# Amplifier.net
KiCad netlist of a schematic drawn in Altium Designer
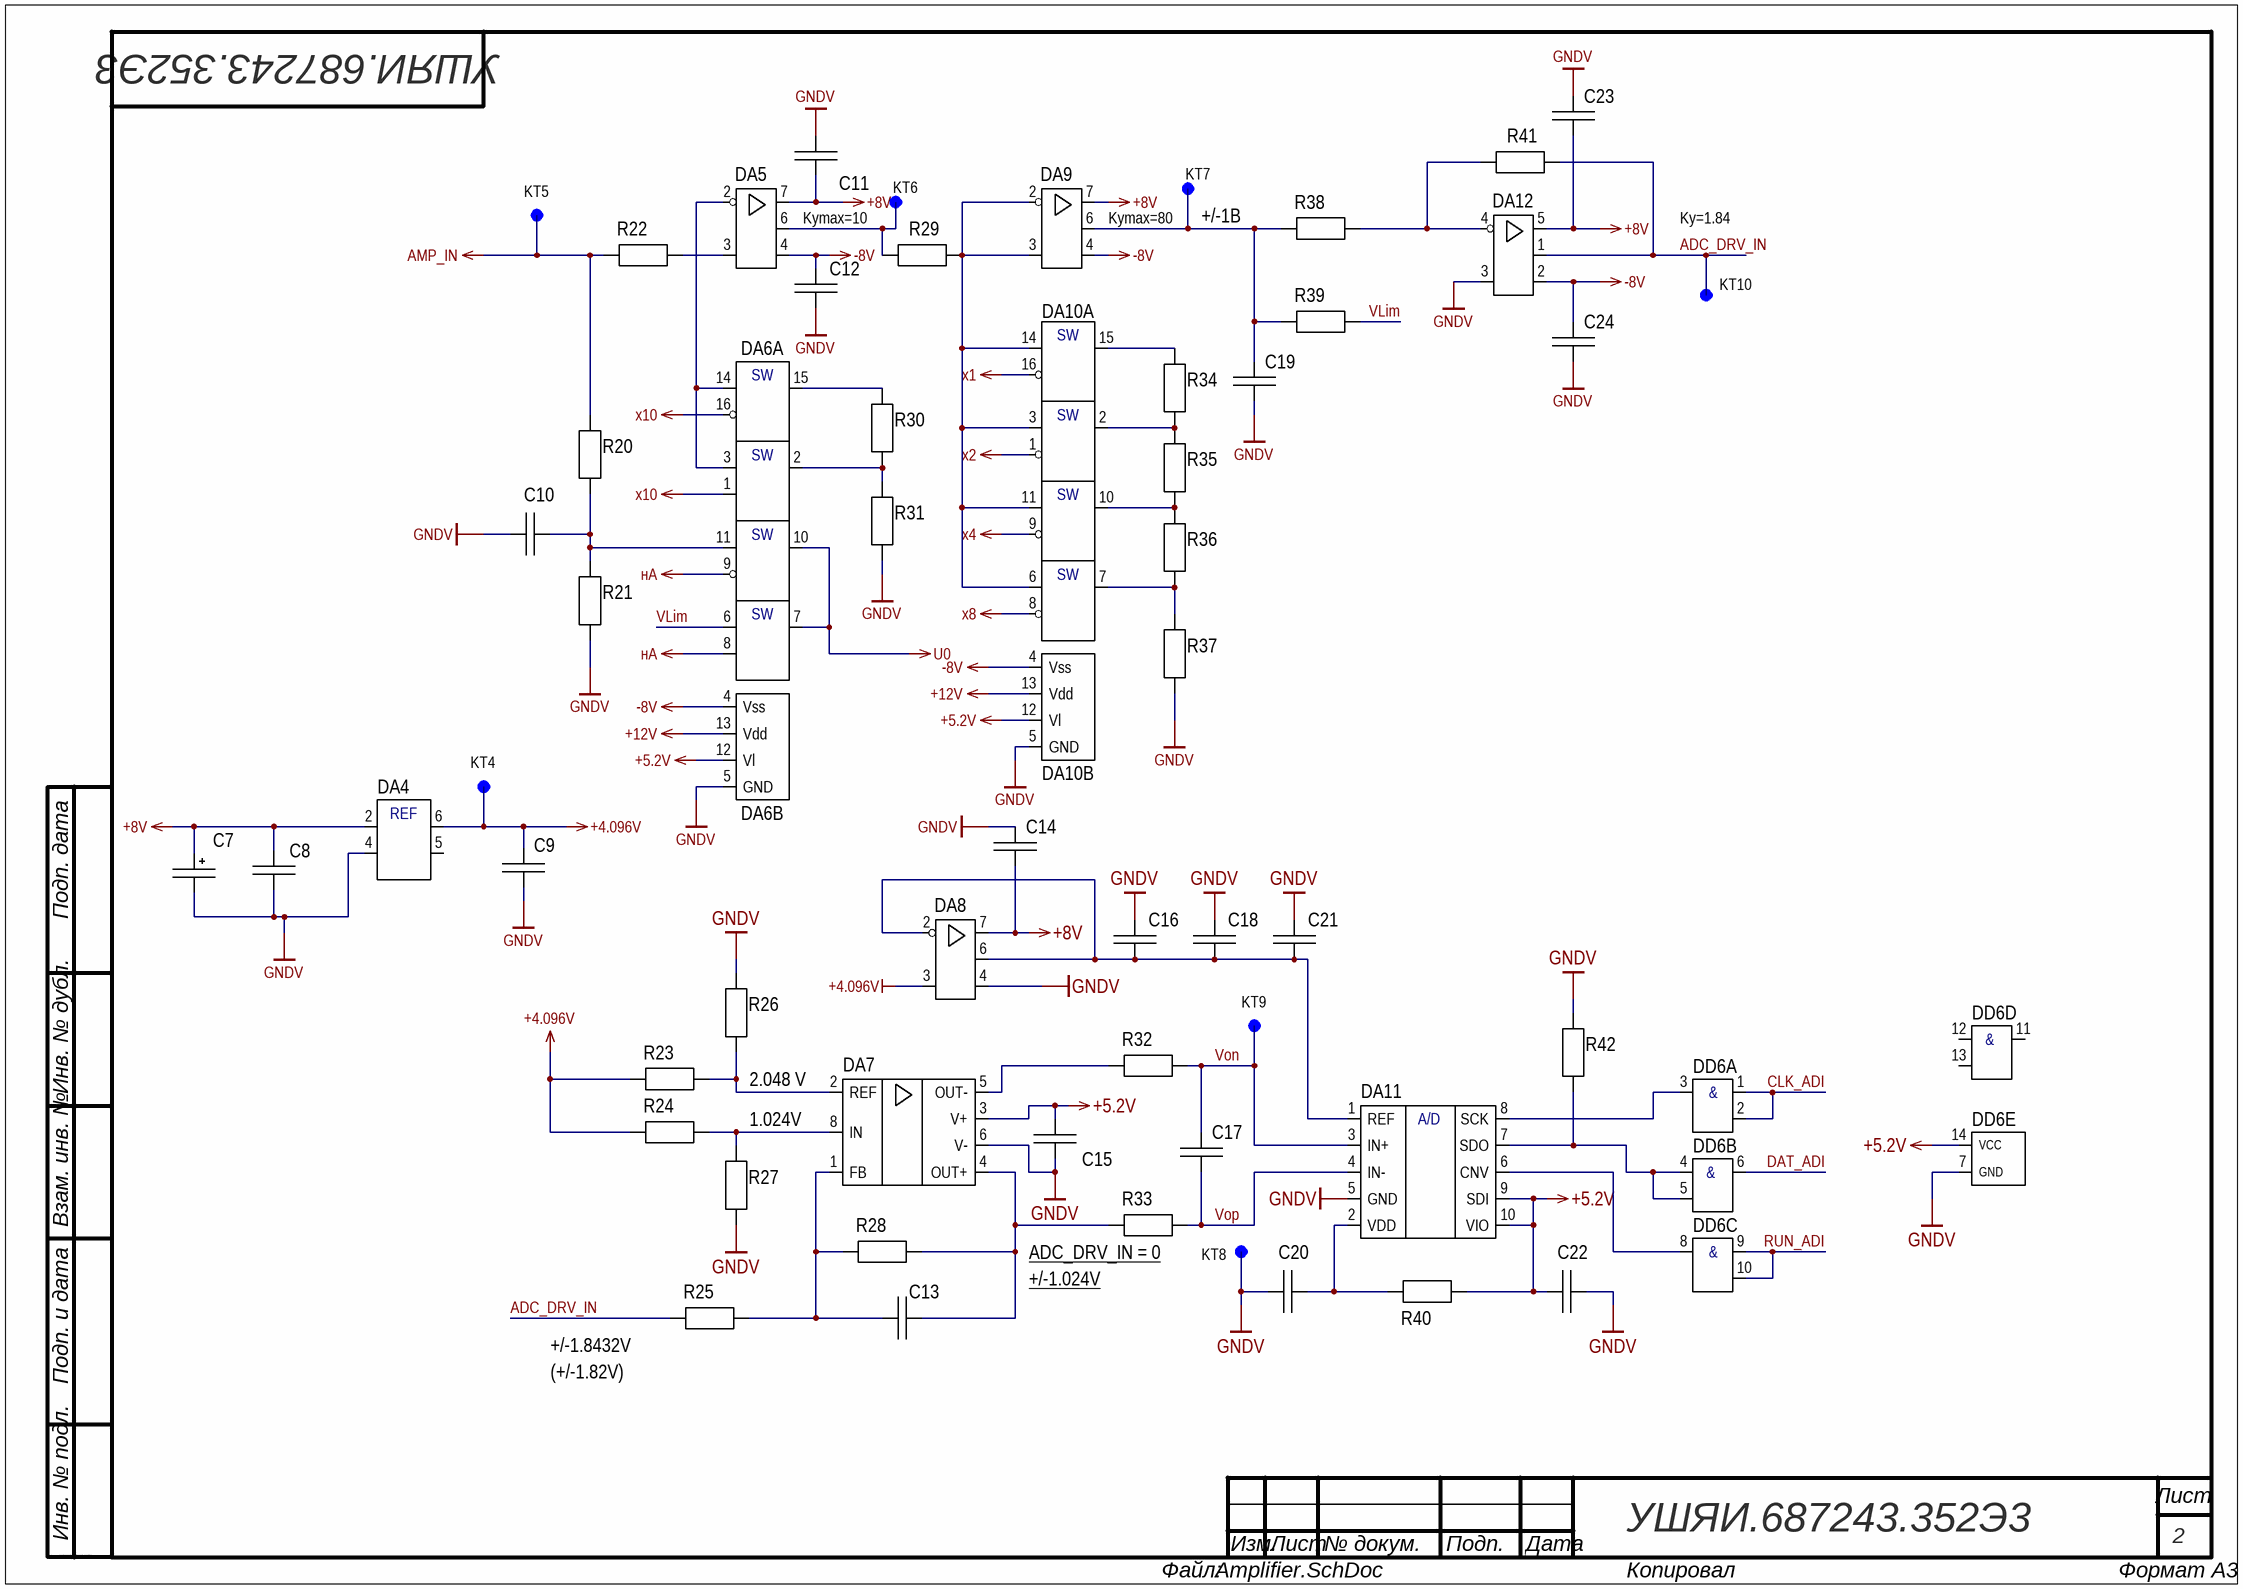
[diagram p0: Amplifier.SchDoc]

(export (version "E")
  (design (tool "Eeschema 10.0.6"))
  (components
    (comp (ref "C7")
      (value "JRB-50В-4,7мкФ")
      (footprint "CAP TH ALUM ELEC D5.00mm S2.00mm H11.00mm")
      (libsource (lib "МНИПИ_Конденсаторы") (part "JRB-50В-4,7мкФ"))
    )
    (comp (ref "C8")
      (value "1206-X7R-50 B-0,1 мкФ+-10%")
      (footprint "standard-case:CAP: 1206")
      (libsource (lib "МНИПИ_Конденсаторы") (part "1206-X7R-50 B-0,1 мкФ+-10%"))
    )
    (comp (ref "C9")
      (value "0805-X7R-25 В-0,1 мкФ +-10%")
      (footprint "standard-case:CAP: 0805")
      (libsource (lib "МНИПИ_Конденсаторы") (part "0805-X7R-25 В-0,1 мкФ +-10%"))
    )
    (comp (ref "C10")
      (value "1206-X7R-50 B-0,01 мкФ+-10%")
      (footprint "standard-case:CAP: 1206")
      (libsource (lib "МНИПИ_Конденсаторы") (part "1206-X7R-50 B-0,01 мкФ+-10%"))
    )
    (comp (ref "C11")
      (value "1206-X7R-50 B-0,1 мкФ+-10%")
      (footprint "standard-case:CAP: 1206")
      (libsource (lib "МНИПИ_Конденсаторы") (part "1206-X7R-50 B-0,1 мкФ+-10%"))
    )
    (comp (ref "C12")
      (value "1206-X7R-50 B-0,1 мкФ+-10%")
      (footprint "standard-case:CAP: 1206")
      (libsource (lib "МНИПИ_Конденсаторы") (part "1206-X7R-50 B-0,1 мкФ+-10%"))
    )
    (comp (ref "C13")
      (value "0805-C0G-50 В-240 пФ +-5%")
      (footprint "standard-case:CAP: 0805")
      (libsource (lib "МНИПИ_Конденсаторы") (part "0805-C0G-50 В-240 пФ +-5%"))
    )
    (comp (ref "C14")
      (value "1206-X7R-50 B-0,1 мкФ+-10%")
      (footprint "standard-case:CAP: 1206")
      (libsource (lib "МНИПИ_Конденсаторы") (part "1206-X7R-50 B-0,1 мкФ+-10%"))
    )
    (comp (ref "C15")
      (value "1206-X7R-50 B-0,1 мкФ+-10%")
      (footprint "standard-case:CAP: 1206")
      (libsource (lib "МНИПИ_Конденсаторы") (part "1206-X7R-50 B-0,1 мкФ+-10%"))
    )
    (comp (ref "C16")
      (value "1206-X7R-10 B-10 мкФ+-10%")
      (footprint "standard-case:CAP: 1206")
      (libsource (lib "МНИПИ_Конденсаторы") (part "1206-X7R-10 B-10 мкФ+-10%"))
    )
    (comp (ref "C17")
      (value "1206-X7R-50 B-0,01 мкФ+-10%")
      (footprint "standard-case:CAP: 1206")
      (libsource (lib "МНИПИ_Конденсаторы") (part "1206-X7R-50 B-0,01 мкФ+-10%"))
    )
    (comp (ref "C18")
      (value "1206-X7R-50 B-2,2 мкФ+-10%")
      (footprint "standard-case:CAP: 1206")
      (libsource (lib "МНИПИ_Конденсаторы") (part "1206-X7R-50 B-2,2 мкФ+-10%"))
    )
    (comp (ref "C19")
      (value "1206-X7R-50 B-0,01 мкФ+-10%")
      (footprint "standard-case:CAP: 1206")
      (libsource (lib "МНИПИ_Конденсаторы") (part "1206-X7R-50 B-0,01 мкФ+-10%"))
    )
    (comp (ref "C20")
      (value "1206-X7R-50 B-2,2 мкФ+-10%")
      (footprint "standard-case:CAP: 1206")
      (libsource (lib "МНИПИ_Конденсаторы") (part "1206-X7R-50 B-2,2 мкФ+-10%"))
    )
    (comp (ref "C21")
      (value "1206-X7R-50 B-2,2 мкФ+-10%")
      (footprint "standard-case:CAP: 1206")
      (libsource (lib "МНИПИ_Конденсаторы") (part "1206-X7R-50 B-2,2 мкФ+-10%"))
    )
    (comp (ref "C22")
      (value "1206-X7R-50 B-0,33 мкФ+-10%")
      (footprint "standard-case:CAP: 1206")
      (libsource (lib "МНИПИ_Конденсаторы") (part "1206-X7R-50 B-0,33 мкФ+-10%"))
    )
    (comp (ref "C23")
      (value "1206-X7R-50 B-0,1 мкФ+-10%")
      (footprint "standard-case:CAP: 1206")
      (libsource (lib "МНИПИ_Конденсаторы") (part "1206-X7R-50 B-0,1 мкФ+-10%"))
    )
    (comp (ref "C24")
      (value "1206-X7R-50 B-0,1 мкФ+-10%")
      (footprint "standard-case:CAP: 1206")
      (libsource (lib "МНИПИ_Конденсаторы") (part "1206-X7R-50 B-0,1 мкФ+-10%"))
    )
    (comp (ref "DA4")
      (value "ADR434BR")
      (footprint "standard-case:8-SOIC")
      (libsource (lib "МНИПИ_Микросхемы") (part "ADR434BR"))
    )
    (comp (ref "DA5")
      (value "ADA4637-1ARZ")
      (footprint "standard-case:8-SOIC")
      (description "30 V, High Speed, Low Noise, Low Bias\r\nCurrent, JFET Operational Amplifier")
      (libsource (lib "МНИПИ_Микросхемы") (part "ADA4637-1ARZ"))
    )
    (comp (ref "DA6")
      (value "ADG433BR")
      (footprint "standard-case:16-SOIC")
      (description "LC2MOS Precision Quad SPST Switches")
      (libsource (lib "МНИПИ_Микросхемы") (part "ADG433BR"))
    )
    (comp (ref "DA7")
      (value "ADA4941-1YRZ")
      (footprint "standard-case:8-SOIC")
      (description "Single-Supply, Differential, 18-Bit ADC Driver")
      (libsource (lib "МНИПИ_Микросхемы") (part "ADA4941-1YRZ"))
    )
    (comp (ref "DA8")
      (value "AD8031BRZ")
      (footprint "standard-case:8-SOIC")
      (description "Rail-to-Rail I/O Amplifiers 2.7 V, 800 μA, 80 MHz")
      (libsource (lib "МНИПИ_Микросхемы") (part "AD8031BRZ"))
    )
    (comp (ref "DA9")
      (value "ADA4637-1ARZ")
      (footprint "standard-case:8-SOIC")
      (description "30 V, High Speed, Low Noise, Low Bias\r\nCurrent, JFET Operational Amplifier")
      (libsource (lib "МНИПИ_Микросхемы") (part "ADA4637-1ARZ"))
    )
    (comp (ref "DA10")
      (value "ADG431BR")
      (footprint "standard-case:16-SOIC")
      (description "LC2MOS Precision Quad SPST Switches")
      (libsource (lib "МНИПИ_Микросхемы") (part "ADG431BR"))
    )
    (comp (ref "DA11")
      (value "AD7691BRM")
      (footprint "10-MSOP")
      (libsource (lib "МНИПИ_Микросхемы") (part "AD7691BRM"))
    )
    (comp (ref "DA12")
      (value "TLV9151IDR")
      (footprint "SOT-23-5")
      (libsource (lib "МНИПИ_Микросхемы") (part "TLV9151IDR"))
    )
    (comp (ref "DD6")
      (value "IN74HC08AD")
      (footprint "standard-case:14-SOIC")
      (description "Quad 2-Input AND Gate High-Performance Silicon-Gate CMOS")
      (libsource (lib "") (part "IN74HC08AD_1"))
    )
    (comp (ref "KT4") (value "OTV10") (footprint "OTV10") (libsource (lib "МНИПИ_Остальное") (part "OTV10")))
    (comp (ref "KT5") (value "OTV10") (footprint "OTV10") (libsource (lib "МНИПИ_Остальное") (part "OTV10")))
    (comp (ref "KT6") (value "OTV10") (footprint "OTV10") (libsource (lib "МНИПИ_Остальное") (part "OTV10")))
    (comp (ref "KT7") (value "OTV10") (footprint "OTV10") (libsource (lib "МНИПИ_Остальное") (part "OTV10")))
    (comp (ref "KT8") (value "OTV10") (footprint "OTV10") (libsource (lib "МНИПИ_Остальное") (part "OTV10")))
    (comp (ref "KT9") (value "OTV10") (footprint "OTV10") (libsource (lib "МНИПИ_Остальное") (part "OTV10")))
    (comp (ref "KT10") (value "OTV10") (footprint "OTV10") (libsource (lib "МНИПИ_Остальное") (part "OTV10")))
    (comp (ref "R20")
      (value "1206-5,1 кОм+-5%")
      (footprint "МНИПИ_Резисторы:1206")
      (libsource (lib "МНИПИ_Резисторы") (part "1206-5,1 кОм+-5%"))
    )
    (comp (ref "R21")
      (value "1206-20 кОм+-5%")
      (footprint "МНИПИ_Резисторы:1206")
      (libsource (lib "МНИПИ_Резисторы") (part "1206-20 кОм+-5%"))
    )
    (comp (ref "R22")
      (value "1206-470 Ом+-5%")
      (footprint "МНИПИ_Резисторы:1206")
      (libsource (lib "МНИПИ_Резисторы") (part "1206-470 Ом+-5%"))
    )
    (comp (ref "R23")
      (value "0805-1 кОм+-0,1%")
      (footprint "МНИПИ_Резисторы:0805")
      (libsource (lib "МНИПИ_Резисторы") (part "0805-1 кОм+-0,1%"))
    )
    (comp (ref "R24")
      (value "0805-1 кОм+-0,1%")
      (footprint "МНИПИ_Резисторы:0805")
      (libsource (lib "МНИПИ_Резисторы") (part "0805-1 кОм+-0,1%"))
    )
    (comp (ref "R25")
      (value "0805-1 кОм+-0,1%")
      (footprint "МНИПИ_Резисторы:0805")
      (libsource (lib "МНИПИ_Резисторы") (part "0805-1 кОм+-0,1%"))
    )
    (comp (ref "R26")
      (value "0805-1 кОм+-0,1%")
      (footprint "МНИПИ_Резисторы:0805")
      (libsource (lib "МНИПИ_Резисторы") (part "0805-1 кОм+-0,1%"))
    )
    (comp (ref "R27")
      (value "0805-332 Ом+-0,1%")
      (footprint "МНИПИ_Резисторы:0805")
      (libsource (lib "МНИПИ_Резисторы") (part "0805-332 Ом+-0,1%"))
    )
    (comp (ref "R28")
      (value "0805-1 кОм+-0,1%")
      (footprint "МНИПИ_Резисторы:0805")
      (libsource (lib "МНИПИ_Резисторы") (part "0805-1 кОм+-0,1%"))
    )
    (comp (ref "R29")
      (value "1206-470 Ом+-5%")
      (footprint "МНИПИ_Резисторы:1206")
      (libsource (lib "МНИПИ_Резисторы") (part "1206-470 Ом+-5%"))
    )
    (comp (ref "R30")
      (value "1206-9,09 кОм+-1%")
      (footprint "МНИПИ_Резисторы:1206")
      (libsource (lib "МНИПИ_Резисторы") (part "1206-9,09 кОм+-1%"))
    )
    (comp (ref "R31")
      (value "1206-1 кОм+-1%")
      (footprint "МНИПИ_Резисторы:1206")
      (libsource (lib "МНИПИ_Резисторы") (part "1206-1 кОм+-1%"))
    )
    (comp (ref "R32")
      (value "1206-51 Ом+-5%")
      (footprint "МНИПИ_Резисторы:1206")
      (libsource (lib "МНИПИ_Резисторы") (part "1206-51 Ом+-5%"))
    )
    (comp (ref "R33")
      (value "1206-51 Ом+-5%")
      (footprint "МНИПИ_Резисторы:1206")
      (libsource (lib "МНИПИ_Резисторы") (part "1206-51 Ом+-5%"))
    )
    (comp (ref "R34")
      (value "1206-4,02 кОм+-0,1%")
      (footprint "МНИПИ_Резисторы:1206")
      (libsource (lib "МНИПИ_Резисторы") (part "1206-4,02 кОм+-0,1%"))
    )
    (comp (ref "R35")
      (value "1206-2 кОм+-0.1%")
      (footprint "МНИПИ_Резисторы:1206")
      (libsource (lib "МНИПИ_Резисторы") (part "1206-2 кОм+-0.1%"))
    )
    (comp (ref "R36")
      (value "1206-1 кОм+-0.1%")
      (footprint "МНИПИ_Резисторы:1206")
      (libsource (lib "МНИПИ_Резисторы") (part "1206-1 кОм+-0.1%"))
    )
    (comp (ref "R37")
      (value "1206-1 кОм+-0.1%")
      (footprint "МНИПИ_Резисторы:1206")
      (libsource (lib "МНИПИ_Резисторы") (part "1206-1 кОм+-0.1%"))
    )
    (comp (ref "R38")
      (value "1206-1 кОм+-0.1%")
      (footprint "МНИПИ_Резисторы:1206")
      (libsource (lib "МНИПИ_Резисторы") (part "1206-1 кОм+-0.1%"))
    )
    (comp (ref "R39")
      (value "1206-5,1 кОм+-5%")
      (footprint "МНИПИ_Резисторы:1206")
      (libsource (lib "МНИПИ_Резисторы") (part "1206-5,1 кОм+-5%"))
    )
    (comp (ref "R40")
      (value "1206-10 Ом+-5%")
      (footprint "МНИПИ_Резисторы:1206")
      (libsource (lib "МНИПИ_Резисторы") (part "1206-10 Ом+-5%"))
    )
    (comp (ref "R41")
      (value "1206-1,82 кОм+-0,1%")
      (footprint "МНИПИ_Резисторы:1206")
      (libsource (lib "МНИПИ_Резисторы") (part "1206-1,82 кОм+-0,1%"))
    )
    (comp (ref "R42")
      (value "1206-10 кОм+-5%")
      (footprint "МНИПИ_Резисторы:1206")
      (libsource (lib "МНИПИ_Резисторы") (part "1206-10 кОм+-5%"))
    )
  )
  (nets
    (net (code "1") (name "+4.096V") (class "Default")
      (node (ref "C9") (pin "2") (pinfunction "2_2") (pintype "passive"))
      (node (ref "DA4") (pin "6") (pinfunction "Vout_6") (pintype "passive"))
      (node (ref "DA8") (pin "3") (pinfunction "+IN_3") (pintype "passive"))
      (node (ref "KT4") (pin "1") (pinfunction "1_1") (pintype "passive"))
      (node (ref "R23") (pin "1") (pintype "passive"))
      (node (ref "R24") (pin "1") (pintype "passive"))
    )
    (net (code "2") (name "+5.2V") (class "Default")
      (node (ref "C15") (pin "1") (pinfunction "1_1") (pintype "passive"))
      (node (ref "C22") (pin "1") (pinfunction "1_1") (pintype "passive"))
      (node (ref "DA10") (pin "12") (pinfunction "Vl_12") (pintype "passive"))
      (node (ref "DA11") (pin "10") (pinfunction "VIO_10") (pintype "passive"))
      (node (ref "DA11") (pin "9") (pinfunction "SDI_9") (pintype "passive"))
      (node (ref "DA6") (pin "12") (pinfunction "Vl_12") (pintype "passive"))
      (node (ref "DA7") (pin "3") (pinfunction "V+_3") (pintype "passive"))
      (node (ref "DD6") (pin "14") (pinfunction "VCC_14") (pintype "passive"))
      (node (ref "R40") (pin "2") (pintype "passive"))
    )
    (net (code "3") (name "+8V") (class "Default")
      (node (ref "C11") (pin "2") (pinfunction "2_2") (pintype "passive"))
      (node (ref "C14") (pin "1") (pinfunction "1_1") (pintype "passive"))
      (node (ref "C23") (pin "1") (pinfunction "1_1") (pintype "passive"))
      (node (ref "C7") (pin "1") (pinfunction "1_1") (pintype "passive"))
      (node (ref "C8") (pin "2") (pinfunction "2_2") (pintype "passive"))
      (node (ref "DA12") (pin "5") (pinfunction "Vs+_5") (pintype "passive"))
      (node (ref "DA4") (pin "2") (pinfunction "+Vin_2") (pintype "passive"))
      (node (ref "DA5") (pin "7") (pinfunction "Vs+_7") (pintype "passive"))
      (node (ref "DA8") (pin "7") (pinfunction "Vs+_7") (pintype "passive"))
      (node (ref "DA9") (pin "7") (pinfunction "Vs+_7") (pintype "passive"))
    )
    (net (code "4") (name "+12V") (class "Default")
      (node (ref "DA10") (pin "13") (pinfunction "Vdd_13") (pintype "passive"))
      (node (ref "DA6") (pin "13") (pinfunction "Vdd_13") (pintype "passive"))
    )
    (net (code "5") (name "-8V") (class "Default")
      (node (ref "C12") (pin "1") (pinfunction "1_1") (pintype "passive"))
      (node (ref "C24") (pin "2") (pinfunction "2_2") (pintype "passive"))
      (node (ref "DA10") (pin "4") (pinfunction "Vss_4") (pintype "passive"))
      (node (ref "DA12") (pin "2") (pinfunction "Vs-_2") (pintype "passive"))
      (node (ref "DA5") (pin "4") (pinfunction "Vs-_4") (pintype "passive"))
      (node (ref "DA6") (pin "4") (pinfunction "Vss_4") (pintype "passive"))
      (node (ref "DA9") (pin "4") (pinfunction "Vs-_4") (pintype "passive"))
    )
    (net (code "6") (name "/ADC_DRV_IN") (class "Default")
      (node (ref "DA12") (pin "1") (pinfunction "OUT_1") (pintype "passive"))
      (node (ref "KT10") (pin "1") (pinfunction "1_1") (pintype "passive"))
      (node (ref "R25") (pin "1") (pintype "passive"))
      (node (ref "R41") (pin "2") (pinfunction "1_2") (pintype "passive"))
    )
    (net (code "7") (name "/CLK_ADI") (class "Default")
      (node (ref "DD6") (pin "1") (pinfunction "A1_1") (pintype "passive"))
      (node (ref "DD6") (pin "2") (pinfunction "B1_2") (pintype "passive"))
    )
    (net (code "8") (name "/DAT_ADI") (class "Default")
      (node (ref "DD6") (pin "6") (pinfunction "Y2_6") (pintype "passive"))
    )
    (net (code "9") (name "/RUN_ADI") (class "Default")
      (node (ref "DD6") (pin "10") (pinfunction "B3_10") (pintype "passive"))
      (node (ref "DD6") (pin "9") (pinfunction "A3_9") (pintype "passive"))
    )
    (net (code "10") (name "/VLim") (class "Default")
      (node (ref "DA6") (pin "6") (pinfunction "S4_6") (pintype "passive"))
      (node (ref "R39") (pin "1") (pinfunction "1_1") (pintype "passive"))
    )
    (net (code "11") (name "/Von") (class "Default")
      (node (ref "C17") (pin "2") (pinfunction "2_2") (pintype "passive"))
      (node (ref "DA11") (pin "3") (pinfunction "IN+_3") (pintype "passive"))
      (node (ref "KT9") (pin "1") (pinfunction "1_1") (pintype "passive"))
      (node (ref "R32") (pin "2") (pinfunction "2_2") (pintype "passive"))
    )
    (net (code "12") (name "/Vop") (class "Default")
      (node (ref "C17") (pin "1") (pinfunction "1_1") (pintype "passive"))
      (node (ref "DA11") (pin "4") (pinfunction "IN-_4") (pintype "passive"))
      (node (ref "R33") (pin "2") (pinfunction "2_2") (pintype "passive"))
    )
    (net (code "13") (name "AMP_IN") (class "Default")
      (node (ref "KT5") (pin "1") (pinfunction "1_1") (pintype "passive"))
      (node (ref "R20") (pin "2") (pinfunction "2_2") (pintype "passive"))
      (node (ref "R22") (pin "1") (pinfunction "1_1") (pintype "passive"))
    )
    (net (code "14") (name "GNDV") (class "Default")
      (node (ref "C10") (pin "2") (pinfunction "2_2") (pintype "passive"))
      (node (ref "C11") (pin "1") (pinfunction "1_1") (pintype "passive"))
      (node (ref "C12") (pin "2") (pinfunction "2_2") (pintype "passive"))
      (node (ref "C14") (pin "2") (pinfunction "2_2") (pintype "passive"))
      (node (ref "C15") (pin "2") (pinfunction "2_2") (pintype "passive"))
      (node (ref "C16") (pin "2") (pinfunction "2_2") (pintype "passive"))
      (node (ref "C18") (pin "2") (pinfunction "2_2") (pintype "passive"))
      (node (ref "C19") (pin "1") (pinfunction "1_1") (pintype "passive"))
      (node (ref "C20") (pin "1") (pinfunction "1_1") (pintype "passive"))
      (node (ref "C21") (pin "2") (pinfunction "2_2") (pintype "passive"))
      (node (ref "C22") (pin "2") (pinfunction "2_2") (pintype "passive"))
      (node (ref "C23") (pin "2") (pinfunction "2_2") (pintype "passive"))
      (node (ref "C24") (pin "1") (pinfunction "1_1") (pintype "passive"))
      (node (ref "C7") (pin "2") (pinfunction "2_2") (pintype "passive"))
      (node (ref "C8") (pin "1") (pinfunction "1_1") (pintype "passive"))
      (node (ref "C9") (pin "1") (pinfunction "1_1") (pintype "passive"))
      (node (ref "DA10") (pin "5") (pinfunction "GND_5") (pintype "passive"))
      (node (ref "DA11") (pin "5") (pinfunction "GND_5") (pintype "passive"))
      (node (ref "DA12") (pin "3") (pinfunction "+IN_3") (pintype "passive"))
      (node (ref "DA4") (pin "4") (pinfunction "GND_4") (pintype "passive"))
      (node (ref "DA6") (pin "5") (pinfunction "GND_5") (pintype "passive"))
      (node (ref "DA7") (pin "6") (pinfunction "V-_6") (pintype "passive"))
      (node (ref "DA8") (pin "4") (pinfunction "Vs-_4") (pintype "passive"))
      (node (ref "DD6") (pin "7") (pinfunction "GND_7") (pintype "passive"))
      (node (ref "KT8") (pin "1") (pinfunction "1_1") (pintype "passive"))
      (node (ref "R21") (pin "1") (pinfunction "1_1") (pintype "passive"))
      (node (ref "R26") (pin "2") (pintype "passive"))
      (node (ref "R27") (pin "1") (pintype "passive"))
      (node (ref "R31") (pin "1") (pinfunction "1_1") (pintype "passive"))
      (node (ref "R37") (pin "1") (pinfunction "1_1") (pintype "passive"))
      (node (ref "R42") (pin "1") (pintype "passive"))
    )
    (net (code "15") (name "Net-(DA5-+IN)") (class "Default")
      (node (ref "DA5") (pin "3") (pinfunction "+IN_3") (pintype "passive"))
      (node (ref "R22") (pin "2") (pinfunction "1_2") (pintype "passive"))
    )
    (net (code "16") (name "Net-(DA5--IN)") (class "Default")
      (node (ref "DA5") (pin "2") (pinfunction "-IN_2") (pintype "passive"))
      (node (ref "DA6") (pin "14") (pinfunction "S2_14") (pintype "passive"))
      (node (ref "DA6") (pin "3") (pinfunction "S1_3") (pintype "passive"))
    )
    (net (code "17") (name "Net-(DA5-OUT)") (class "Default")
      (node (ref "DA5") (pin "6") (pinfunction "OUT_6") (pintype "passive"))
      (node (ref "KT6") (pin "1") (pinfunction "1_1") (pintype "passive"))
      (node (ref "R29") (pin "1") (pinfunction "1_1") (pintype "passive"))
    )
    (net (code "18") (name "Net-(DA6A-D1)") (class "Default")
      (node (ref "DA6") (pin "2") (pinfunction "D1_2") (pintype "passive"))
      (node (ref "R30") (pin "1") (pinfunction "1_1") (pintype "passive"))
      (node (ref "R31") (pin "2") (pinfunction "2_2") (pintype "passive"))
    )
    (net (code "19") (name "Net-(DA6A-D2)") (class "Default")
      (node (ref "DA6") (pin "15") (pinfunction "D2_15") (pintype "passive"))
      (node (ref "R30") (pin "2") (pinfunction "2_2") (pintype "passive"))
    )
    (net (code "20") (name "Net-(DA6A-S3)") (class "Default")
      (node (ref "C10") (pin "1") (pinfunction "1_1") (pintype "passive"))
      (node (ref "DA6") (pin "11") (pinfunction "S3_11") (pintype "passive"))
      (node (ref "R20") (pin "1") (pinfunction "1_1") (pintype "passive"))
      (node (ref "R21") (pin "2") (pinfunction "2_2") (pintype "passive"))
    )
    (net (code "21") (name "Net-(DA7-FB)") (class "Default")
      (node (ref "C13") (pin "1") (pinfunction "1_1") (pintype "passive"))
      (node (ref "DA7") (pin "1") (pinfunction "FB_1") (pintype "passive"))
      (node (ref "R25") (pin "2") (pintype "passive"))
      (node (ref "R28") (pin "1") (pintype "passive"))
    )
    (net (code "22") (name "Net-(DA7-IN)") (class "Default")
      (node (ref "DA7") (pin "8") (pinfunction "IN_8") (pintype "passive"))
      (node (ref "R24") (pin "2") (pintype "passive"))
      (node (ref "R27") (pin "2") (pintype "passive"))
    )
    (net (code "23") (name "Net-(DA7-OUT+)") (class "Default")
      (node (ref "C13") (pin "2") (pinfunction "2_2") (pintype "passive"))
      (node (ref "DA7") (pin "4") (pinfunction "OUT+_4") (pintype "passive"))
      (node (ref "R28") (pin "2") (pintype "passive"))
      (node (ref "R33") (pin "1") (pinfunction "1_1") (pintype "passive"))
    )
    (net (code "24") (name "Net-(DA7-OUT-)") (class "Default")
      (node (ref "DA7") (pin "5") (pinfunction "OUT-_5") (pintype "passive"))
      (node (ref "R32") (pin "1") (pinfunction "1_1") (pintype "passive"))
    )
    (net (code "25") (name "Net-(DA7-REF)") (class "Default")
      (node (ref "DA7") (pin "2") (pinfunction "REF_2") (pintype "passive"))
      (node (ref "R23") (pin "2") (pintype "passive"))
      (node (ref "R26") (pin "1") (pintype "passive"))
    )
    (net (code "26") (name "Net-(DA9-OUT)") (class "Default")
      (node (ref "C19") (pin "2") (pinfunction "2_2") (pintype "passive"))
      (node (ref "DA9") (pin "6") (pinfunction "OUT_6") (pintype "passive"))
      (node (ref "KT7") (pin "1") (pinfunction "1_1") (pintype "passive"))
      (node (ref "R38") (pin "1") (pinfunction "1_1") (pintype "passive"))
      (node (ref "R39") (pin "2") (pinfunction "2_2") (pintype "passive"))
    )
    (net (code "27") (name "Net-(DA10A-D1)") (class "Default")
      (node (ref "DA10") (pin "2") (pinfunction "D1_2") (pintype "passive"))
      (node (ref "R34") (pin "1") (pinfunction "1_1") (pintype "passive"))
      (node (ref "R35") (pin "2") (pinfunction "2_2") (pintype "passive"))
    )
    (net (code "28") (name "Net-(DA10A-D2)") (class "Default")
      (node (ref "DA10") (pin "15") (pinfunction "D2_15") (pintype "passive"))
      (node (ref "R34") (pin "2") (pinfunction "2_2") (pintype "passive"))
    )
    (net (code "29") (name "Net-(DA10A-D3)") (class "Default")
      (node (ref "DA10") (pin "10") (pinfunction "D3_10") (pintype "passive"))
      (node (ref "R35") (pin "1") (pinfunction "1_1") (pintype "passive"))
      (node (ref "R36") (pin "2") (pinfunction "2_2") (pintype "passive"))
    )
    (net (code "30") (name "Net-(DA10A-D4)") (class "Default")
      (node (ref "DA10") (pin "7") (pinfunction "D4_7") (pintype "passive"))
      (node (ref "R36") (pin "1") (pinfunction "1_1") (pintype "passive"))
      (node (ref "R37") (pin "2") (pinfunction "2_2") (pintype "passive"))
    )
    (net (code "31") (name "Net-(DA10A-S1)") (class "Default")
      (node (ref "DA10") (pin "11") (pinfunction "S3_11") (pintype "passive"))
      (node (ref "DA10") (pin "14") (pinfunction "S2_14") (pintype "passive"))
      (node (ref "DA10") (pin "3") (pinfunction "S1_3") (pintype "passive"))
      (node (ref "DA10") (pin "6") (pinfunction "S4_6") (pintype "passive"))
      (node (ref "DA9") (pin "2") (pinfunction "-IN_2") (pintype "passive"))
      (node (ref "DA9") (pin "3") (pinfunction "+IN_3") (pintype "passive"))
      (node (ref "R29") (pin "2") (pinfunction "1_2") (pintype "passive"))
    )
    (net (code "32") (name "Net-(DA11-CNV)") (class "Default")
      (node (ref "DA11") (pin "6") (pinfunction "CNV_6") (pintype "passive"))
      (node (ref "DD6") (pin "8") (pinfunction "Y3_8") (pintype "passive"))
    )
    (net (code "33") (name "Net-(DA11-REF)") (class "Default")
      (node (ref "C16") (pin "1") (pinfunction "1_1") (pintype "passive"))
      (node (ref "C18") (pin "1") (pinfunction "1_1") (pintype "passive"))
      (node (ref "C21") (pin "1") (pinfunction "1_1") (pintype "passive"))
      (node (ref "DA11") (pin "1") (pinfunction "REF_1") (pintype "passive"))
      (node (ref "DA8") (pin "2") (pinfunction "-IN_2") (pintype "passive"))
      (node (ref "DA8") (pin "6") (pinfunction "OUT_6") (pintype "passive"))
    )
    (net (code "34") (name "Net-(DA11-SCK)") (class "Default")
      (node (ref "DA11") (pin "8") (pinfunction "SCK_8") (pintype "passive"))
      (node (ref "DD6") (pin "3") (pinfunction "Y1_3") (pintype "passive"))
    )
    (net (code "35") (name "Net-(DA11-SDO)") (class "Default")
      (node (ref "DA11") (pin "7") (pinfunction "SDO_7") (pintype "passive"))
      (node (ref "DD6") (pin "4") (pinfunction "A2_4") (pintype "passive"))
      (node (ref "DD6") (pin "5") (pinfunction "B2_5") (pintype "passive"))
      (node (ref "R42") (pin "2") (pintype "passive"))
    )
    (net (code "36") (name "Net-(DA11-VDD)") (class "Default")
      (node (ref "C20") (pin "2") (pinfunction "2_2") (pintype "passive"))
      (node (ref "DA11") (pin "2") (pinfunction "VDD_2") (pintype "passive"))
      (node (ref "R40") (pin "1") (pintype "passive"))
    )
    (net (code "37") (name "Net-(DA12--IN)") (class "Default")
      (node (ref "DA12") (pin "4") (pinfunction "-IN_4") (pintype "passive"))
      (node (ref "R38") (pin "2") (pinfunction "2_2") (pintype "passive"))
      (node (ref "R41") (pin "1") (pinfunction "1_1") (pintype "passive"))
    )
    (net (code "38") (name "U0") (class "Default")
      (node (ref "DA6") (pin "10") (pinfunction "D3_10") (pintype "passive"))
      (node (ref "DA6") (pin "7") (pinfunction "D4_7") (pintype "passive"))
    )
    (net (code "39") (name "unconnected-(DA4-TRIM-Pad5)") (class "Default")
      (node (ref "DA4") (pin "5") (pinfunction "TRIM_5") (pintype "passive"))
    )
    (net (code "40") (name "unconnected-(DD6D-A4-Pad12)") (class "Default")
      (node (ref "DD6") (pin "12") (pinfunction "A4_12") (pintype "passive"))
    )
    (net (code "41") (name "unconnected-(DD6D-B4-Pad13)") (class "Default")
      (node (ref "DD6") (pin "13") (pinfunction "B4_13") (pintype "passive"))
    )
    (net (code "42") (name "unconnected-(DD6D-Y4-Pad11)") (class "Default")
      (node (ref "DD6") (pin "11") (pinfunction "Y4_11") (pintype "passive"))
    )
    (net (code "43") (name "x1") (class "Default")
      (node (ref "DA10") (pin "16") (pinfunction "IN2_16") (pintype "passive"))
    )
    (net (code "44") (name "x2") (class "Default")
      (node (ref "DA10") (pin "1") (pinfunction "IN1_1") (pintype "passive"))
    )
    (net (code "45") (name "x4") (class "Default")
      (node (ref "DA10") (pin "9") (pinfunction "IN3_9") (pintype "passive"))
    )
    (net (code "46") (name "x8") (class "Default")
      (node (ref "DA10") (pin "8") (pinfunction "IN4_8") (pintype "passive"))
    )
    (net (code "47") (name "x10") (class "Default")
      (node (ref "DA6") (pin "1") (pinfunction "IN1_1") (pintype "passive"))
      (node (ref "DA6") (pin "16") (pinfunction "IN2_16") (pintype "passive"))
    )
    (net (code "48") (name "нА") (class "Default")
      (node (ref "DA6") (pin "8") (pinfunction "IN4_8") (pintype "passive"))
      (node (ref "DA6") (pin "9") (pinfunction "IN3_9") (pintype "passive"))
    )
  )
)
